# Power.net
KiCad netlist of a schematic drawn in Altium Designer
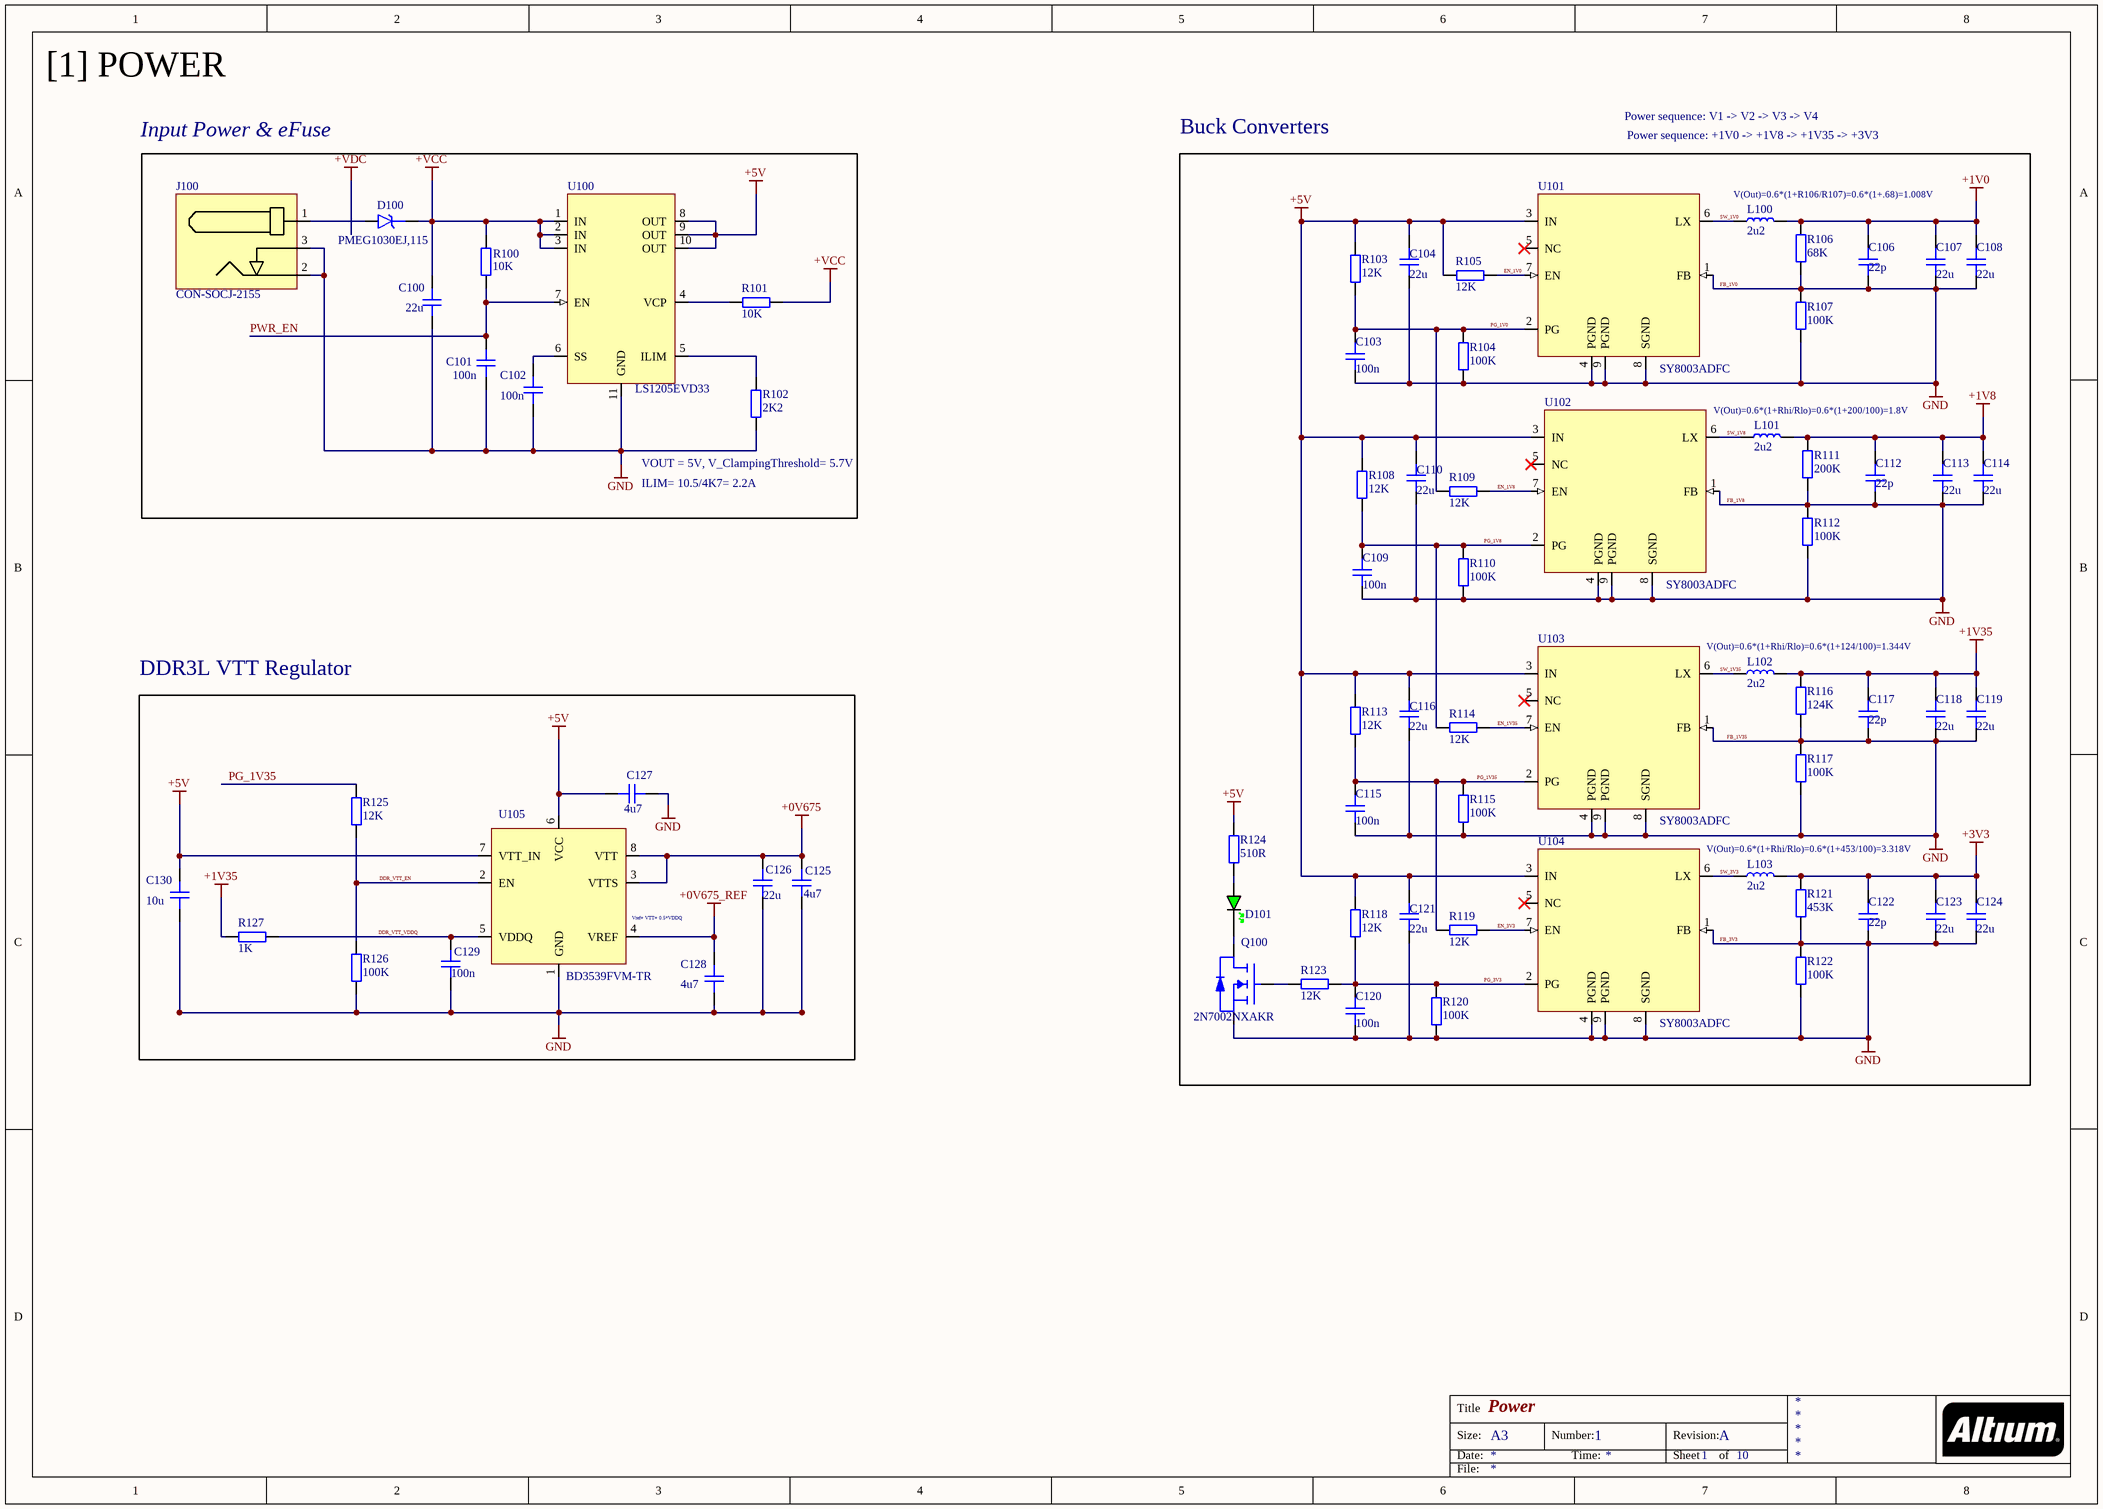
[diagram p0: Power.SchDoc]

(export (version "E")
  (design (tool "Eeschema 10.0.6"))
  (components
    (comp (ref "C100")
      (value "22u")
      (footprint "CAP_1210")
      (description "Capacitor SMD 1210")
      (libsource (lib "Schematic-Lib-PhilsLab") (part "CAP_1210"))
    )
    (comp (ref "C101")
      (value "100n")
      (footprint "CAP_1210")
      (description "Capacitor SMD 1210")
      (libsource (lib "Schematic-Lib-PhilsLab") (part "CAP_1210"))
    )
    (comp (ref "C102")
      (value "100n")
      (footprint "CAP_1210")
      (description "Capacitor SMD 1210")
      (libsource (lib "Schematic-Lib-PhilsLab") (part "CAP_1210"))
    )
    (comp (ref "C103")
      (value "100n")
      (footprint "CAP_1210")
      (description "Capacitor SMD 1210")
      (libsource (lib "Schematic-Lib-PhilsLab") (part "CAP_1210"))
    )
    (comp (ref "C104")
      (value "22u")
      (footprint "CAP_1210")
      (description "Capacitor SMD 1210")
      (libsource (lib "Schematic-Lib-PhilsLab") (part "CAP_1210"))
    )
    (comp (ref "C106")
      (value "22p")
      (footprint "CAP_1210")
      (description "Capacitor SMD 1210")
      (libsource (lib "Schematic-Lib-PhilsLab") (part "CAP_1210"))
    )
    (comp (ref "C107")
      (value "22u")
      (footprint "CAP_1210")
      (description "Capacitor SMD 1210")
      (libsource (lib "Schematic-Lib-PhilsLab") (part "CAP_1210"))
    )
    (comp (ref "C108")
      (value "22u")
      (footprint "CAP_1210")
      (description "Capacitor SMD 1210")
      (libsource (lib "Schematic-Lib-PhilsLab") (part "CAP_1210"))
    )
    (comp (ref "C109")
      (value "100n")
      (footprint "CAP_1210")
      (description "Capacitor SMD 1210")
      (libsource (lib "Schematic-Lib-PhilsLab") (part "CAP_1210"))
    )
    (comp (ref "C110")
      (value "22u")
      (footprint "CAP_1210")
      (description "Capacitor SMD 1210")
      (libsource (lib "Schematic-Lib-PhilsLab") (part "CAP_1210"))
    )
    (comp (ref "C112")
      (value "22p")
      (footprint "CAP_1210")
      (description "Capacitor SMD 1210")
      (libsource (lib "Schematic-Lib-PhilsLab") (part "CAP_1210"))
    )
    (comp (ref "C113")
      (value "22u")
      (footprint "CAP_1210")
      (description "Capacitor SMD 1210")
      (libsource (lib "Schematic-Lib-PhilsLab") (part "CAP_1210"))
    )
    (comp (ref "C114")
      (value "22u")
      (footprint "CAP_1210")
      (description "Capacitor SMD 1210")
      (libsource (lib "Schematic-Lib-PhilsLab") (part "CAP_1210"))
    )
    (comp (ref "C115")
      (value "100n")
      (footprint "CAP_1210")
      (description "Capacitor SMD 1210")
      (libsource (lib "Schematic-Lib-PhilsLab") (part "CAP_1210"))
    )
    (comp (ref "C116")
      (value "22u")
      (footprint "CAP_1210")
      (description "Capacitor SMD 1210")
      (libsource (lib "Schematic-Lib-PhilsLab") (part "CAP_1210"))
    )
    (comp (ref "C117")
      (value "22p")
      (footprint "CAP_1210")
      (description "Capacitor SMD 1210")
      (libsource (lib "Schematic-Lib-PhilsLab") (part "CAP_1210"))
    )
    (comp (ref "C118")
      (value "22u")
      (footprint "CAP_1210")
      (description "Capacitor SMD 1210")
      (libsource (lib "Schematic-Lib-PhilsLab") (part "CAP_1210"))
    )
    (comp (ref "C119")
      (value "22u")
      (footprint "CAP_1210")
      (description "Capacitor SMD 1210")
      (libsource (lib "Schematic-Lib-PhilsLab") (part "CAP_1210"))
    )
    (comp (ref "C120")
      (value "100n")
      (footprint "CAP_1210")
      (description "Capacitor SMD 1210")
      (libsource (lib "Schematic-Lib-PhilsLab") (part "CAP_1210"))
    )
    (comp (ref "C121")
      (value "22u")
      (footprint "CAP_1210")
      (description "Capacitor SMD 1210")
      (libsource (lib "Schematic-Lib-PhilsLab") (part "CAP_1210"))
    )
    (comp (ref "C122")
      (value "22p")
      (footprint "CAP_1210")
      (description "Capacitor SMD 1210")
      (libsource (lib "Schematic-Lib-PhilsLab") (part "CAP_1210"))
    )
    (comp (ref "C123")
      (value "22u")
      (footprint "CAP_1210")
      (description "Capacitor SMD 1210")
      (libsource (lib "Schematic-Lib-PhilsLab") (part "CAP_1210"))
    )
    (comp (ref "C124")
      (value "22u")
      (footprint "CAP_1210")
      (description "Capacitor SMD 1210")
      (libsource (lib "Schematic-Lib-PhilsLab") (part "CAP_1210"))
    )
    (comp (ref "C125")
      (value "4u7")
      (footprint "CAP_1210")
      (description "Capacitor SMD 1210")
      (libsource (lib "Schematic-Lib-PhilsLab") (part "CAP_1210"))
    )
    (comp (ref "C126")
      (value "22u")
      (footprint "CAP_1210")
      (description "Capacitor SMD 1210")
      (libsource (lib "Schematic-Lib-PhilsLab") (part "CAP_1210"))
    )
    (comp (ref "C127")
      (value "4u7")
      (footprint "CAP_1210")
      (description "Capacitor SMD 1210")
      (libsource (lib "Schematic-Lib-PhilsLab") (part "CAP_1210"))
    )
    (comp (ref "C128")
      (value "4u7")
      (footprint "CAP_1210")
      (description "Capacitor SMD 1210")
      (libsource (lib "Schematic-Lib-PhilsLab") (part "CAP_1210"))
    )
    (comp (ref "C129")
      (value "100n")
      (footprint "CAP_1210")
      (description "Capacitor SMD 1210")
      (libsource (lib "Schematic-Lib-PhilsLab") (part "CAP_1210"))
    )
    (comp (ref "C130")
      (value "10u")
      (footprint "CAP_1210")
      (description "Capacitor SMD 1210")
      (libsource (lib "Schematic-Lib-PhilsLab") (part "CAP_1210"))
    )
    (comp (ref "D100")
      (value "PMEG1030EJ,115")
      (footprint "SOD-323")
      (description "Diode Zener SMD SOD-323")
      (libsource (lib "Schematic-Lib-PhilsLab") (part "D_ZENER_SOD_323"))
    )
    (comp (ref "D101")
      (value "GREEN")
      (footprint "LED_0402_GREEN")
      (description "LED 0402 GREEN SMD")
      (libsource (lib "Schematic-Lib-PhilsLab") (part "LED_0402_GREEN"))
    )
    (comp (ref "J100")
      (value "CON-SOCJ-2155")
      (footprint "CON-SOCJ-2155")
      (description "DC Barrell Jack 2.1mm 30V 2.5A THT")
      (fields (field (name "MANUFACTURER") "Gravitech"))
      (libsource (lib "Schematic-Lib-PhilsLab") (part "CON-SOCJ-2155"))
    )
    (comp (ref "L100")
      (value "2u2")
      (footprint "NRS5020")
      (description "NRS5020 SMD Power Inductor Taiyo Yuden")
      (fields (field (name "MANUFACTURER") "Taiyo Yuden") (field (name "MANUFACTURER PART NUMBER") "NRS5020"))
      (libsource (lib "Schematic-Lib-PhilsLab") (part "NRS5020"))
    )
    (comp (ref "L101")
      (value "2u2")
      (footprint "NRS5020")
      (description "NRS5020 SMD Power Inductor Taiyo Yuden")
      (fields (field (name "MANUFACTURER") "Taiyo Yuden") (field (name "MANUFACTURER PART NUMBER") "NRS5020"))
      (libsource (lib "Schematic-Lib-PhilsLab") (part "NRS5020"))
    )
    (comp (ref "L102")
      (value "2u2")
      (footprint "NRS5020")
      (description "NRS5020 SMD Power Inductor Taiyo Yuden")
      (fields (field (name "MANUFACTURER") "Taiyo Yuden") (field (name "MANUFACTURER PART NUMBER") "NRS5020"))
      (libsource (lib "Schematic-Lib-PhilsLab") (part "NRS5020"))
    )
    (comp (ref "L103")
      (value "2u2")
      (footprint "NRS5020")
      (description "NRS5020 SMD Power Inductor Taiyo Yuden")
      (fields (field (name "MANUFACTURER") "Taiyo Yuden") (field (name "MANUFACTURER PART NUMBER") "NRS5020"))
      (libsource (lib "Schematic-Lib-PhilsLab") (part "NRS5020"))
    )
    (comp (ref "Q100")
      (value "2N7002NXAKR")
      (footprint "SSM3J338R,LF-SOT23-F")
      (description "MOSFET N-Channel Vds=60V Id=300mA with ESD Protection")
      (fields (field (name "MANUFACTURER") "Nexperia"))
      (libsource (lib "Schematic-Lib-PhilsLab") (part "2N7002NXAKR"))
    )
    (comp (ref "R100")
      (value "10K")
      (footprint "RES_0402")
      (description "Resistor SMD 0402")
      (libsource (lib "Schematic-Lib-PhilsLab") (part "RES_0402"))
    )
    (comp (ref "R101")
      (value "10K")
      (footprint "RES_0402")
      (description "Resistor SMD 0402")
      (libsource (lib "Schematic-Lib-PhilsLab") (part "RES_0402"))
    )
    (comp (ref "R102")
      (value "2K2")
      (footprint "RES_0402")
      (description "Resistor SMD 0402")
      (libsource (lib "Schematic-Lib-PhilsLab") (part "RES_0402"))
    )
    (comp (ref "R103")
      (value "12K")
      (footprint "RES_0402")
      (description "Resistor SMD 0402")
      (libsource (lib "Schematic-Lib-PhilsLab") (part "RES_0402"))
    )
    (comp (ref "R104")
      (value "100K")
      (footprint "RES_0402")
      (description "Resistor SMD 0402")
      (libsource (lib "Schematic-Lib-PhilsLab") (part "RES_0402"))
    )
    (comp (ref "R105")
      (value "12K")
      (footprint "RES_0402")
      (description "Resistor SMD 0402")
      (libsource (lib "Schematic-Lib-PhilsLab") (part "RES_0402"))
    )
    (comp (ref "R106")
      (value "68K")
      (footprint "RES_0402")
      (description "Resistor SMD 0402")
      (libsource (lib "Schematic-Lib-PhilsLab") (part "RES_0402"))
    )
    (comp (ref "R107")
      (value "100K")
      (footprint "RES_0402")
      (description "Resistor SMD 0402")
      (libsource (lib "Schematic-Lib-PhilsLab") (part "RES_0402"))
    )
    (comp (ref "R108")
      (value "12K")
      (footprint "RES_0402")
      (description "Resistor SMD 0402")
      (libsource (lib "Schematic-Lib-PhilsLab") (part "RES_0402"))
    )
    (comp (ref "R109")
      (value "12K")
      (footprint "RES_0402")
      (description "Resistor SMD 0402")
      (libsource (lib "Schematic-Lib-PhilsLab") (part "RES_0402"))
    )
    (comp (ref "R110")
      (value "100K")
      (footprint "RES_0402")
      (description "Resistor SMD 0402")
      (libsource (lib "Schematic-Lib-PhilsLab") (part "RES_0402"))
    )
    (comp (ref "R111")
      (value "200K")
      (footprint "RES_0402")
      (description "Resistor SMD 0402")
      (libsource (lib "Schematic-Lib-PhilsLab") (part "RES_0402"))
    )
    (comp (ref "R112")
      (value "100K")
      (footprint "RES_0402")
      (description "Resistor SMD 0402")
      (libsource (lib "Schematic-Lib-PhilsLab") (part "RES_0402"))
    )
    (comp (ref "R113")
      (value "12K")
      (footprint "RES_0402")
      (description "Resistor SMD 0402")
      (libsource (lib "Schematic-Lib-PhilsLab") (part "RES_0402"))
    )
    (comp (ref "R114")
      (value "12K")
      (footprint "RES_0402")
      (description "Resistor SMD 0402")
      (libsource (lib "Schematic-Lib-PhilsLab") (part "RES_0402"))
    )
    (comp (ref "R115")
      (value "100K")
      (footprint "RES_0402")
      (description "Resistor SMD 0402")
      (libsource (lib "Schematic-Lib-PhilsLab") (part "RES_0402"))
    )
    (comp (ref "R116")
      (value "124K")
      (footprint "RES_0402")
      (description "Resistor SMD 0402")
      (libsource (lib "Schematic-Lib-PhilsLab") (part "RES_0402"))
    )
    (comp (ref "R117")
      (value "100K")
      (footprint "RES_0402")
      (description "Resistor SMD 0402")
      (libsource (lib "Schematic-Lib-PhilsLab") (part "RES_0402"))
    )
    (comp (ref "R118")
      (value "12K")
      (footprint "RES_0402")
      (description "Resistor SMD 0402")
      (libsource (lib "Schematic-Lib-PhilsLab") (part "RES_0402"))
    )
    (comp (ref "R119")
      (value "12K")
      (footprint "RES_0402")
      (description "Resistor SMD 0402")
      (libsource (lib "Schematic-Lib-PhilsLab") (part "RES_0402"))
    )
    (comp (ref "R120")
      (value "100K")
      (footprint "RES_0402")
      (description "Resistor SMD 0402")
      (libsource (lib "Schematic-Lib-PhilsLab") (part "RES_0402"))
    )
    (comp (ref "R121")
      (value "453K")
      (footprint "RES_0402")
      (description "Resistor SMD 0402")
      (libsource (lib "Schematic-Lib-PhilsLab") (part "RES_0402"))
    )
    (comp (ref "R122")
      (value "100K")
      (footprint "RES_0402")
      (description "Resistor SMD 0402")
      (libsource (lib "Schematic-Lib-PhilsLab") (part "RES_0402"))
    )
    (comp (ref "R123")
      (value "12K")
      (footprint "RES_0402")
      (description "Resistor SMD 0402")
      (libsource (lib "Schematic-Lib-PhilsLab") (part "RES_0402"))
    )
    (comp (ref "R124")
      (value "510R")
      (footprint "RES_0402")
      (description "Resistor SMD 0402")
      (libsource (lib "Schematic-Lib-PhilsLab") (part "RES_0402"))
    )
    (comp (ref "R125")
      (value "12K")
      (footprint "RES_0402")
      (description "Resistor SMD 0402")
      (libsource (lib "Schematic-Lib-PhilsLab") (part "RES_0402"))
    )
    (comp (ref "R126")
      (value "100K")
      (footprint "RES_0402")
      (description "Resistor SMD 0402")
      (libsource (lib "Schematic-Lib-PhilsLab") (part "RES_0402"))
    )
    (comp (ref "R127")
      (value "1K")
      (footprint "RES_0402")
      (description "Resistor SMD 0402")
      (libsource (lib "Schematic-Lib-PhilsLab") (part "RES_0402"))
    )
    (comp (ref "U100")
      (value "LS1205EVD33")
      (footprint "DFN3x3_10L")
      (description "18V, 5A eFuse with Programmable Current Limit and Output Voltage Clamp")
      (fields (field (name "MANUFACTURER") "Littelfuse"))
      (libsource (lib "Schematic-Lib-PhilsLab") (part "LS1205EVD33"))
    )
    (comp (ref "U101")
      (value "SY8003ADFC")
      (footprint "DFN2x2-8")
      (description "High Efficiency 5.5V, 3A Continuous, 1MHz Synchronous Step Down Regulator")
      (fields
        (field (name "MANUFACTURER") "Silergy")
        (field (name "MANUFACTURER PART NUMBER") "High Efficiency 5.5V, 3A continuous, 1MHz")
      )
      (libsource (lib "Schematic-Lib-PhilsLab") (part "SY8003ADFC"))
    )
    (comp (ref "U102")
      (value "SY8003ADFC")
      (footprint "DFN2x2-8")
      (description "High Efficiency 5.5V, 3A Continuous, 1MHz Synchronous Step Down Regulator")
      (fields
        (field (name "MANUFACTURER") "Silergy")
        (field (name "MANUFACTURER PART NUMBER") "High Efficiency 5.5V, 3A continuous, 1MHz")
      )
      (libsource (lib "Schematic-Lib-PhilsLab") (part "SY8003ADFC"))
    )
    (comp (ref "U103")
      (value "SY8003ADFC")
      (footprint "DFN2x2-8")
      (description "High Efficiency 5.5V, 3A Continuous, 1MHz Synchronous Step Down Regulator")
      (fields
        (field (name "MANUFACTURER") "Silergy")
        (field (name "MANUFACTURER PART NUMBER") "High Efficiency 5.5V, 3A continuous, 1MHz")
      )
      (libsource (lib "Schematic-Lib-PhilsLab") (part "SY8003ADFC"))
    )
    (comp (ref "U104")
      (value "SY8003ADFC")
      (footprint "DFN2x2-8")
      (description "High Efficiency 5.5V, 3A Continuous, 1MHz Synchronous Step Down Regulator")
      (fields
        (field (name "MANUFACTURER") "Silergy")
        (field (name "MANUFACTURER PART NUMBER") "High Efficiency 5.5V, 3A continuous, 1MHz")
      )
      (libsource (lib "Schematic-Lib-PhilsLab") (part "SY8003ADFC"))
    )
    (comp (ref "U105")
      (value "BD3539FVM-TR")
      (footprint "MSOP8")
      (description "1.0V to 5.5V, 1A 1Ch Termination Regulator for DDR-SDRAMs")
      (fields (field (name "MANUFACTURER") "ROHM Semiconductor"))
      (libsource (lib "Schematic-Lib-PhilsLab") (part "BD3539FVM-TR"))
    )
  )
  (nets
    (net (code "1") (name "+0V675") (class "Default")
      (node (ref "C125") (pin "2") (pinfunction "2_2") (pintype "passive"))
      (node (ref "C126") (pin "2") (pinfunction "2_2") (pintype "passive"))
      (node (ref "U105") (pin "3") (pinfunction "VTTS_3") (pintype "passive"))
      (node (ref "U105") (pin "8") (pinfunction "VTT_8") (pintype "passive"))
    )
    (net (code "2") (name "+0V675_REF") (class "Default")
      (node (ref "C128") (pin "2") (pinfunction "2_2") (pintype "passive"))
      (node (ref "U105") (pin "4") (pinfunction "VREF_4") (pintype "passive"))
    )
    (net (code "3") (name "+1V0") (class "Default")
      (node (ref "C106") (pin "2") (pinfunction "2_2") (pintype "passive"))
      (node (ref "C107") (pin "2") (pinfunction "2_2") (pintype "passive"))
      (node (ref "C108") (pin "2") (pinfunction "2_2") (pintype "passive"))
      (node (ref "L100") (pin "2") (pinfunction "2_2") (pintype "passive"))
      (node (ref "R106") (pin "1") (pinfunction "1_1") (pintype "passive"))
    )
    (net (code "4") (name "+1V8") (class "Default")
      (node (ref "C112") (pin "2") (pinfunction "2_2") (pintype "passive"))
      (node (ref "C113") (pin "2") (pinfunction "2_2") (pintype "passive"))
      (node (ref "C114") (pin "2") (pinfunction "2_2") (pintype "passive"))
      (node (ref "L101") (pin "2") (pinfunction "2_2") (pintype "passive"))
      (node (ref "R111") (pin "1") (pinfunction "1_1") (pintype "passive"))
    )
    (net (code "5") (name "+1V35") (class "Default")
      (node (ref "C117") (pin "2") (pinfunction "2_2") (pintype "passive"))
      (node (ref "C118") (pin "2") (pinfunction "2_2") (pintype "passive"))
      (node (ref "C119") (pin "2") (pinfunction "2_2") (pintype "passive"))
      (node (ref "L102") (pin "2") (pinfunction "2_2") (pintype "passive"))
      (node (ref "R116") (pin "1") (pinfunction "1_1") (pintype "passive"))
      (node (ref "R127") (pin "1") (pinfunction "1_1") (pintype "passive"))
    )
    (net (code "6") (name "+3V3") (class "Default")
      (node (ref "C122") (pin "2") (pinfunction "2_2") (pintype "passive"))
      (node (ref "C123") (pin "2") (pinfunction "2_2") (pintype "passive"))
      (node (ref "C124") (pin "2") (pinfunction "2_2") (pintype "passive"))
      (node (ref "L103") (pin "2") (pinfunction "2_2") (pintype "passive"))
      (node (ref "R121") (pin "1") (pinfunction "1_1") (pintype "passive"))
    )
    (net (code "7") (name "+5V") (class "Default")
      (node (ref "C104") (pin "2") (pinfunction "2_2") (pintype "passive"))
      (node (ref "C110") (pin "2") (pinfunction "2_2") (pintype "passive"))
      (node (ref "C116") (pin "2") (pinfunction "2_2") (pintype "passive"))
      (node (ref "C121") (pin "2") (pinfunction "2_2") (pintype "passive"))
      (node (ref "C127") (pin "2") (pinfunction "2_2") (pintype "passive"))
      (node (ref "C130") (pin "2") (pinfunction "2_2") (pintype "passive"))
      (node (ref "R103") (pin "1") (pinfunction "1_1") (pintype "passive"))
      (node (ref "R105") (pin "1") (pinfunction "1_1") (pintype "passive"))
      (node (ref "R108") (pin "1") (pinfunction "1_1") (pintype "passive"))
      (node (ref "R113") (pin "1") (pinfunction "1_1") (pintype "passive"))
      (node (ref "R118") (pin "1") (pinfunction "1_1") (pintype "passive"))
      (node (ref "R124") (pin "2") (pinfunction "2_2") (pintype "passive"))
      (node (ref "U100") (pin "10") (pinfunction "OUT_10") (pintype "power_in"))
      (node (ref "U100") (pin "8") (pinfunction "OUT_8") (pintype "power_in"))
      (node (ref "U100") (pin "9") (pinfunction "OUT_9") (pintype "power_in"))
      (node (ref "U101") (pin "3") (pinfunction "IN_3") (pintype "power_in"))
      (node (ref "U102") (pin "3") (pinfunction "IN_3") (pintype "power_in"))
      (node (ref "U103") (pin "3") (pinfunction "IN_3") (pintype "power_in"))
      (node (ref "U104") (pin "3") (pinfunction "IN_3") (pintype "power_in"))
      (node (ref "U105") (pin "6") (pinfunction "VCC_6") (pintype "passive"))
      (node (ref "U105") (pin "7") (pinfunction "VTT_IN_7") (pintype "passive"))
    )
    (net (code "8") (name "+VCC") (class "Default")
      (node (ref "C100") (pin "2") (pinfunction "2_2") (pintype "passive"))
      (node (ref "D100") (pin "K") (pinfunction "K_K") (pintype "passive"))
      (node (ref "R100") (pin "2") (pinfunction "2_2") (pintype "passive"))
      (node (ref "R101") (pin "1") (pinfunction "1_1") (pintype "passive"))
      (node (ref "U100") (pin "1") (pinfunction "IN_1") (pintype "power_in"))
      (node (ref "U100") (pin "2") (pinfunction "IN_2") (pintype "power_in"))
      (node (ref "U100") (pin "3") (pinfunction "IN_3") (pintype "power_in"))
    )
    (net (code "10") (name "/DDR_VTT_EN") (class "Default")
      (node (ref "R125") (pin "2") (pinfunction "2_2") (pintype "passive"))
      (node (ref "R126") (pin "1") (pinfunction "1_1") (pintype "passive"))
      (node (ref "U105") (pin "2") (pinfunction "EN_2") (pintype "passive"))
    )
    (net (code "11") (name "/DDR_VTT_VDDQ") (class "Default")
      (node (ref "C129") (pin "2") (pinfunction "2_2") (pintype "passive"))
      (node (ref "R127") (pin "2") (pinfunction "2_2") (pintype "passive"))
      (node (ref "U105") (pin "5") (pinfunction "VDDQ_5") (pintype "passive"))
    )
    (net (code "12") (name "/EN_1V0") (class "Default")
      (node (ref "R105") (pin "2") (pinfunction "2_2") (pintype "passive"))
      (node (ref "U101") (pin "7") (pinfunction "EN_7") (pintype "input"))
    )
    (net (code "13") (name "/EN_1V8") (class "Default")
      (node (ref "R109") (pin "2") (pinfunction "2_2") (pintype "passive"))
      (node (ref "U102") (pin "7") (pinfunction "EN_7") (pintype "input"))
    )
    (net (code "14") (name "/EN_1V35") (class "Default")
      (node (ref "R114") (pin "2") (pinfunction "2_2") (pintype "passive"))
      (node (ref "U103") (pin "7") (pinfunction "EN_7") (pintype "input"))
    )
    (net (code "15") (name "/EN_3V3") (class "Default")
      (node (ref "R119") (pin "2") (pinfunction "2_2") (pintype "passive"))
      (node (ref "U104") (pin "7") (pinfunction "EN_7") (pintype "input"))
    )
    (net (code "16") (name "/PG_1V0") (class "Default")
      (node (ref "C103") (pin "2") (pinfunction "2_2") (pintype "passive"))
      (node (ref "R103") (pin "2") (pinfunction "2_2") (pintype "passive"))
      (node (ref "R104") (pin "1") (pinfunction "1_1") (pintype "passive"))
      (node (ref "R109") (pin "1") (pinfunction "1_1") (pintype "passive"))
      (node (ref "U101") (pin "2") (pinfunction "PG_2") (pintype "open_collector"))
    )
    (net (code "17") (name "/PG_1V8") (class "Default")
      (node (ref "C109") (pin "2") (pinfunction "2_2") (pintype "passive"))
      (node (ref "R108") (pin "2") (pinfunction "2_2") (pintype "passive"))
      (node (ref "R110") (pin "1") (pinfunction "1_1") (pintype "passive"))
      (node (ref "R114") (pin "1") (pinfunction "1_1") (pintype "passive"))
      (node (ref "U102") (pin "2") (pinfunction "PG_2") (pintype "open_collector"))
    )
    (net (code "18") (name "/PG_1V35") (class "Default")
      (node (ref "C115") (pin "2") (pinfunction "2_2") (pintype "passive"))
      (node (ref "R113") (pin "2") (pinfunction "2_2") (pintype "passive"))
      (node (ref "R115") (pin "1") (pinfunction "1_1") (pintype "passive"))
      (node (ref "R119") (pin "1") (pinfunction "1_1") (pintype "passive"))
      (node (ref "R125") (pin "1") (pinfunction "1_1") (pintype "passive"))
      (node (ref "U103") (pin "2") (pinfunction "PG_2") (pintype "open_collector"))
    )
    (net (code "19") (name "/PG_3V3") (class "Default")
      (node (ref "C120") (pin "2") (pinfunction "2_2") (pintype "passive"))
      (node (ref "R118") (pin "2") (pinfunction "2_2") (pintype "passive"))
      (node (ref "R120") (pin "1") (pinfunction "1_1") (pintype "passive"))
      (node (ref "R123") (pin "2") (pinfunction "2_2") (pintype "passive"))
      (node (ref "U104") (pin "2") (pinfunction "PG_2") (pintype "open_collector"))
    )
    (net (code "20") (name "/PWR_EN") (class "Default")
      (node (ref "C101") (pin "2") (pinfunction "2_2") (pintype "passive"))
      (node (ref "R100") (pin "1") (pinfunction "1_1") (pintype "passive"))
      (node (ref "U100") (pin "7") (pinfunction "EN_7") (pintype "input"))
    )
    (net (code "21") (name "/SW_1V0") (class "Default")
      (node (ref "L100") (pin "1") (pinfunction "1_1") (pintype "passive"))
      (node (ref "U101") (pin "6") (pinfunction "LX_6") (pintype "power_in"))
    )
    (net (code "22") (name "/SW_1V8") (class "Default")
      (node (ref "L101") (pin "1") (pinfunction "1_1") (pintype "passive"))
      (node (ref "U102") (pin "6") (pinfunction "LX_6") (pintype "power_in"))
    )
    (net (code "23") (name "/SW_1V35") (class "Default")
      (node (ref "L102") (pin "1") (pinfunction "1_1") (pintype "passive"))
      (node (ref "U103") (pin "6") (pinfunction "LX_6") (pintype "power_in"))
    )
    (net (code "24") (name "/SW_3V3") (class "Default")
      (node (ref "L103") (pin "1") (pinfunction "1_1") (pintype "passive"))
      (node (ref "U104") (pin "6") (pinfunction "LX_6") (pintype "power_in"))
    )
    (net (code "25") (name "GND") (class "Default")
      (node (ref "C100") (pin "1") (pinfunction "1_1") (pintype "passive"))
      (node (ref "C101") (pin "1") (pinfunction "1_1") (pintype "passive"))
      (node (ref "C102") (pin "1") (pinfunction "1_1") (pintype "passive"))
      (node (ref "C103") (pin "1") (pinfunction "1_1") (pintype "passive"))
      (node (ref "C104") (pin "1") (pinfunction "1_1") (pintype "passive"))
      (node (ref "C106") (pin "1") (pinfunction "1_1") (pintype "passive"))
      (node (ref "C107") (pin "1") (pinfunction "1_1") (pintype "passive"))
      (node (ref "C108") (pin "1") (pinfunction "1_1") (pintype "passive"))
      (node (ref "C109") (pin "1") (pinfunction "1_1") (pintype "passive"))
      (node (ref "C110") (pin "1") (pinfunction "1_1") (pintype "passive"))
      (node (ref "C112") (pin "1") (pinfunction "1_1") (pintype "passive"))
      (node (ref "C113") (pin "1") (pinfunction "1_1") (pintype "passive"))
      (node (ref "C114") (pin "1") (pinfunction "1_1") (pintype "passive"))
      (node (ref "C115") (pin "1") (pinfunction "1_1") (pintype "passive"))
      (node (ref "C116") (pin "1") (pinfunction "1_1") (pintype "passive"))
      (node (ref "C117") (pin "1") (pinfunction "1_1") (pintype "passive"))
      (node (ref "C118") (pin "1") (pinfunction "1_1") (pintype "passive"))
      (node (ref "C119") (pin "1") (pinfunction "1_1") (pintype "passive"))
      (node (ref "C120") (pin "1") (pinfunction "1_1") (pintype "passive"))
      (node (ref "C121") (pin "1") (pinfunction "1_1") (pintype "passive"))
      (node (ref "C122") (pin "1") (pinfunction "1_1") (pintype "passive"))
      (node (ref "C123") (pin "1") (pinfunction "1_1") (pintype "passive"))
      (node (ref "C124") (pin "1") (pinfunction "1_1") (pintype "passive"))
      (node (ref "C125") (pin "1") (pinfunction "1_1") (pintype "passive"))
      (node (ref "C126") (pin "1") (pinfunction "1_1") (pintype "passive"))
      (node (ref "C127") (pin "1") (pinfunction "1_1") (pintype "passive"))
      (node (ref "C128") (pin "1") (pinfunction "1_1") (pintype "passive"))
      (node (ref "C129") (pin "1") (pinfunction "1_1") (pintype "passive"))
      (node (ref "C130") (pin "1") (pinfunction "1_1") (pintype "passive"))
      (node (ref "J100") (pin "2") (pinfunction "2_2") (pintype "passive"))
      (node (ref "J100") (pin "3") (pinfunction "3_3") (pintype "passive"))
      (node (ref "Q100") (pin "S") (pinfunction "S_S") (pintype "passive"))
      (node (ref "R102") (pin "2") (pinfunction "2_2") (pintype "passive"))
      (node (ref "R104") (pin "2") (pinfunction "2_2") (pintype "passive"))
      (node (ref "R106") (pin "2") (pinfunction "2_2") (pintype "passive"))
      (node (ref "R107") (pin "1") (pinfunction "1_1") (pintype "passive"))
      (node (ref "R107") (pin "2") (pinfunction "2_2") (pintype "passive"))
      (node (ref "R110") (pin "2") (pinfunction "2_2") (pintype "passive"))
      (node (ref "R111") (pin "2") (pinfunction "2_2") (pintype "passive"))
      (node (ref "R112") (pin "1") (pinfunction "1_1") (pintype "passive"))
      (node (ref "R112") (pin "2") (pinfunction "2_2") (pintype "passive"))
      (node (ref "R115") (pin "2") (pinfunction "2_2") (pintype "passive"))
      (node (ref "R116") (pin "2") (pinfunction "2_2") (pintype "passive"))
      (node (ref "R117") (pin "1") (pinfunction "1_1") (pintype "passive"))
      (node (ref "R117") (pin "2") (pinfunction "2_2") (pintype "passive"))
      (node (ref "R120") (pin "2") (pinfunction "2_2") (pintype "passive"))
      (node (ref "R121") (pin "2") (pinfunction "2_2") (pintype "passive"))
      (node (ref "R122") (pin "1") (pinfunction "1_1") (pintype "passive"))
      (node (ref "R122") (pin "2") (pinfunction "2_2") (pintype "passive"))
      (node (ref "R126") (pin "2") (pinfunction "2_2") (pintype "passive"))
      (node (ref "U100") (pin "11") (pinfunction "GND_11") (pintype "power_in"))
      (node (ref "U101") (pin "1") (pinfunction "FB_1") (pintype "input"))
      (node (ref "U101") (pin "4") (pinfunction "PGND_4") (pintype "power_in"))
      (node (ref "U101") (pin "8") (pinfunction "SGND_8") (pintype "power_in"))
      (node (ref "U101") (pin "9") (pinfunction "PGND_9") (pintype "power_in"))
      (node (ref "U102") (pin "1") (pinfunction "FB_1") (pintype "input"))
      (node (ref "U102") (pin "4") (pinfunction "PGND_4") (pintype "power_in"))
      (node (ref "U102") (pin "8") (pinfunction "SGND_8") (pintype "power_in"))
      (node (ref "U102") (pin "9") (pinfunction "PGND_9") (pintype "power_in"))
      (node (ref "U103") (pin "1") (pinfunction "FB_1") (pintype "input"))
      (node (ref "U103") (pin "4") (pinfunction "PGND_4") (pintype "power_in"))
      (node (ref "U103") (pin "8") (pinfunction "SGND_8") (pintype "power_in"))
      (node (ref "U103") (pin "9") (pinfunction "PGND_9") (pintype "power_in"))
      (node (ref "U104") (pin "1") (pinfunction "FB_1") (pintype "input"))
      (node (ref "U104") (pin "4") (pinfunction "PGND_4") (pintype "power_in"))
      (node (ref "U104") (pin "8") (pinfunction "SGND_8") (pintype "power_in"))
      (node (ref "U104") (pin "9") (pinfunction "PGND_9") (pintype "power_in"))
      (node (ref "U105") (pin "1") (pinfunction "GND_1") (pintype "passive"))
    )
    (net (code "26") (name "Net-(D100-PadA)") (class "Default")
      (node (ref "D100") (pin "A") (pinfunction "A_A") (pintype "passive"))
      (node (ref "J100") (pin "1") (pinfunction "1_1") (pintype "passive"))
    )
    (net (code "27") (name "Net-(D101-PadA)") (class "Default")
      (node (ref "D101") (pin "A") (pinfunction "A_A") (pintype "passive"))
      (node (ref "R124") (pin "1") (pinfunction "1_1") (pintype "passive"))
    )
    (net (code "28") (name "Net-(D101-PadK)") (class "Default")
      (node (ref "D101") (pin "K") (pinfunction "K_K") (pintype "passive"))
      (node (ref "Q100") (pin "D") (pinfunction "D_D") (pintype "passive"))
    )
    (net (code "29") (name "Net-(Q100-PadG)") (class "Default")
      (node (ref "Q100") (pin "G") (pinfunction "G_G") (pintype "passive"))
      (node (ref "R123") (pin "1") (pinfunction "1_1") (pintype "passive"))
    )
    (net (code "30") (name "Net-(U100-ILIM)") (class "Default")
      (node (ref "R102") (pin "1") (pinfunction "1_1") (pintype "passive"))
      (node (ref "U100") (pin "5") (pinfunction "ILIM_5") (pintype "passive"))
    )
    (net (code "31") (name "Net-(U100-SS)") (class "Default")
      (node (ref "C102") (pin "2") (pinfunction "2_2") (pintype "passive"))
      (node (ref "U100") (pin "6") (pinfunction "SS_6") (pintype "passive"))
    )
    (net (code "32") (name "Net-(U100-VCP)") (class "Default")
      (node (ref "R101") (pin "2") (pinfunction "2_2") (pintype "passive"))
      (node (ref "U100") (pin "4") (pinfunction "VCP_4") (pintype "passive"))
    )
    (net (code "33") (name "unconnected-(U101-NC-Pad5)") (class "Default")
      (node (ref "U101") (pin "5") (pinfunction "NC_5") (pintype "passive+no_connect"))
    )
    (net (code "34") (name "unconnected-(U102-NC-Pad5)") (class "Default")
      (node (ref "U102") (pin "5") (pinfunction "NC_5") (pintype "passive+no_connect"))
    )
    (net (code "35") (name "unconnected-(U103-NC-Pad5)") (class "Default")
      (node (ref "U103") (pin "5") (pinfunction "NC_5") (pintype "passive+no_connect"))
    )
    (net (code "36") (name "unconnected-(U104-NC-Pad5)") (class "Default")
      (node (ref "U104") (pin "5") (pinfunction "NC_5") (pintype "passive+no_connect"))
    )
  )
)
